# Q1_STM32_Buck_MCU.net
KiCad netlist of a schematic drawn in Altium Designer
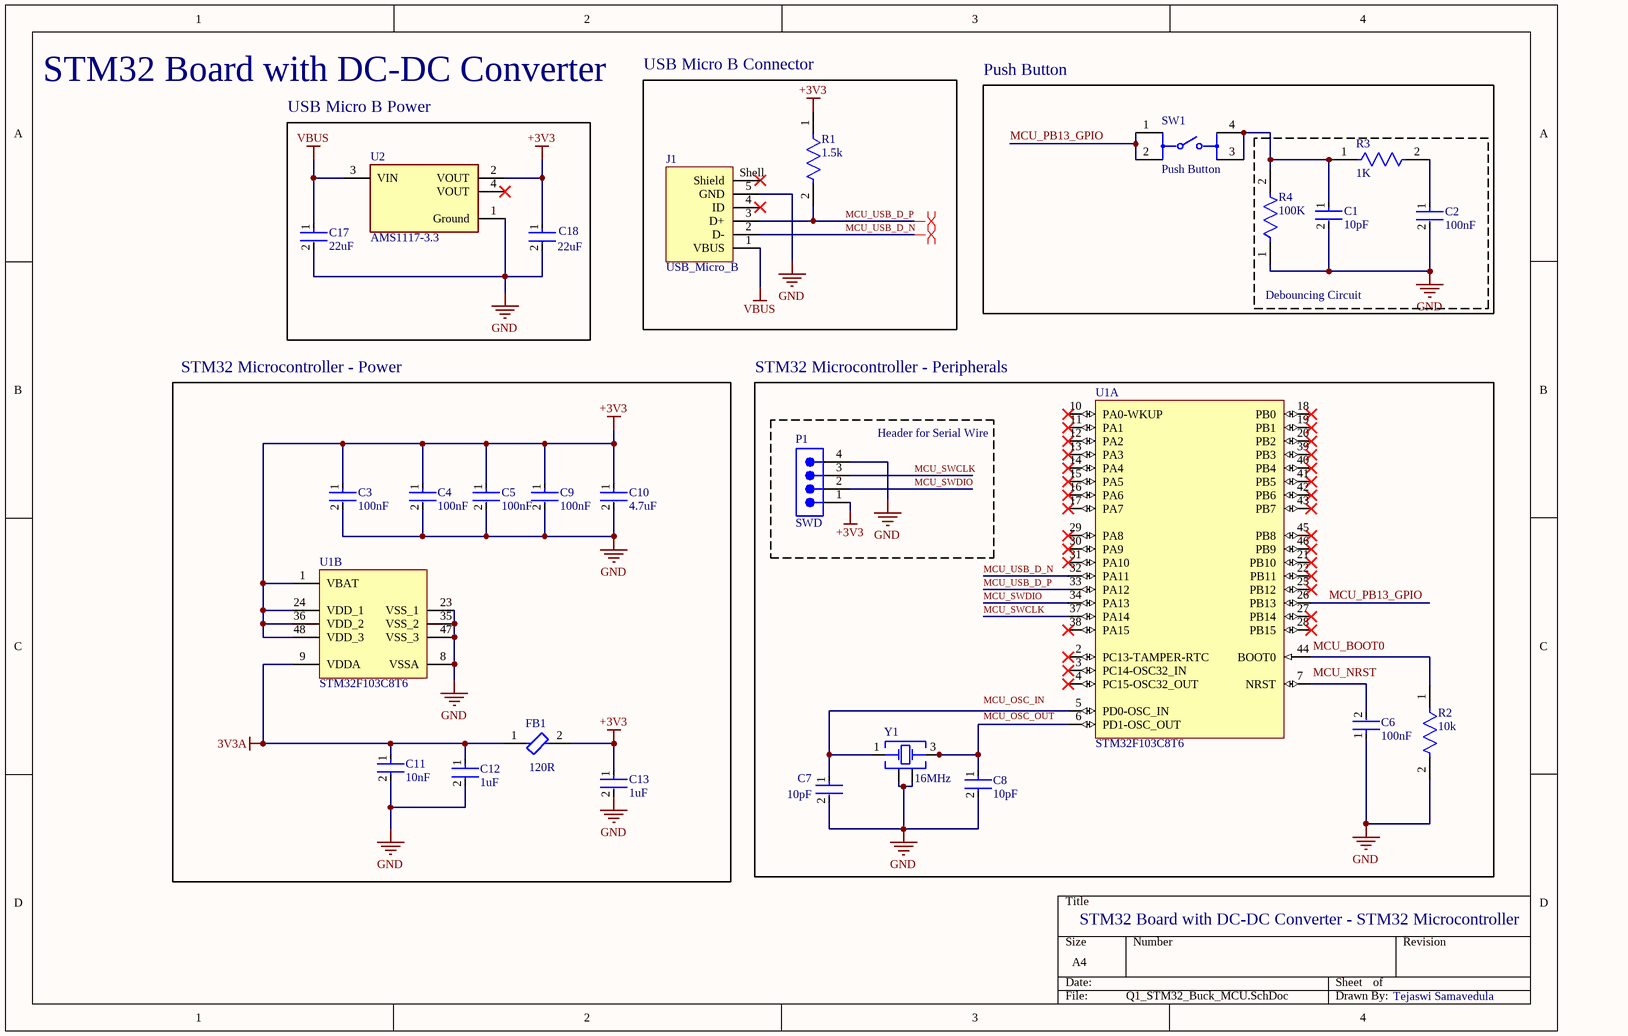
[diagram p0: Q1_STM32_Buck_MCU.SchDoc]

(export (version "E")
  (design (tool "Eeschema 10.0.6"))
  (components
    (comp (ref "C1")
      (value "10pF")
      (footprint "FP-CC0402-MFG")
      (description "CAP CER 0.1UF 16V X5R 0402")
      (fields
        (field (name "OCTOPART") "https://octopart.com/cc0402mrx5r7bb104-yageo-33242280")
        (field (name "MANUFACTURER PART NUMBER") "CC0402MRX5R7BB104")
      )
      (libsource (lib "Altium Content Vault") (part "11868f565c42a9108669ba33697ecf6"))
    )
    (comp (ref "C2")
      (value "100nF")
      (footprint "FP-CC0402-MFG")
      (description "CAP CER 0.1UF 16V X5R 0402")
      (fields
        (field (name "OCTOPART") "https://octopart.com/cc0402mrx5r7bb104-yageo-33242280")
        (field (name "MANUFACTURER PART NUMBER") "CC0402MRX5R7BB104")
      )
      (libsource (lib "Altium Content Vault") (part "11868f565c42a9108669ba33697ecf6"))
    )
    (comp (ref "C3")
      (value "100nF")
      (footprint "FP-CC0402-MFG")
      (description "CAP CER 0.1UF 16V X5R 0402")
      (fields
        (field (name "OCTOPART") "https://octopart.com/cc0402mrx5r7bb104-yageo-33242280")
        (field (name "MANUFACTURER PART NUMBER") "CC0402MRX5R7BB104")
      )
      (libsource (lib "Altium Content Vault") (part "11868f565c42a9108669ba33697ecf6"))
    )
    (comp (ref "C4")
      (value "100nF")
      (footprint "FP-CC0402-MFG")
      (description "CAP CER 0.1UF 16V X5R 0402")
      (fields
        (field (name "OCTOPART") "https://octopart.com/cc0402mrx5r7bb104-yageo-33242280")
        (field (name "MANUFACTURER PART NUMBER") "CC0402MRX5R7BB104")
      )
      (libsource (lib "Altium Content Vault") (part "11868f565c42a9108669ba33697ecf6"))
    )
    (comp (ref "C5")
      (value "100nF")
      (footprint "FP-CC0402-MFG")
      (description "CAP CER 0.1UF 16V X5R 0402")
      (fields
        (field (name "OCTOPART") "https://octopart.com/cc0402mrx5r7bb104-yageo-33242280")
        (field (name "MANUFACTURER PART NUMBER") "CC0402MRX5R7BB104")
      )
      (libsource (lib "Altium Content Vault") (part "11868f565c42a9108669ba33697ecf6"))
    )
    (comp (ref "C6")
      (value "100nF")
      (footprint "FP-CC0402-MFG")
      (description "CAP CER 0.1UF 16V X5R 0402")
      (fields
        (field (name "OCTOPART") "https://octopart.com/cc0402mrx5r7bb104-yageo-33242280")
        (field (name "MANUFACTURER PART NUMBER") "CC0402MRX5R7BB104")
      )
      (libsource (lib "Altium Content Vault") (part "11868f565c42a9108669ba33697ecf6"))
    )
    (comp (ref "C7")
      (value "10pF")
      (footprint "FP-CC0402-MFG")
      (description "CAP CER 0.1UF 16V X5R 0402")
      (fields
        (field (name "OCTOPART") "https://octopart.com/cc0402mrx5r7bb104-yageo-33242280")
        (field (name "MANUFACTURER PART NUMBER") "CC0402MRX5R7BB104")
      )
      (libsource (lib "Altium Content Vault") (part "11868f565c42a9108669ba33697ecf6"))
    )
    (comp (ref "C8")
      (value "10pF")
      (footprint "FP-CC0402-MFG")
      (description "CAP CER 0.1UF 16V X5R 0402")
      (fields
        (field (name "OCTOPART") "https://octopart.com/cc0402mrx5r7bb104-yageo-33242280")
        (field (name "MANUFACTURER PART NUMBER") "CC0402MRX5R7BB104")
      )
      (libsource (lib "Altium Content Vault") (part "11868f565c42a9108669ba33697ecf6"))
    )
    (comp (ref "C9")
      (value "100nF")
      (footprint "FP-CC0402-MFG")
      (description "CAP CER 0.1UF 16V X5R 0402")
      (fields
        (field (name "OCTOPART") "https://octopart.com/cc0402mrx5r7bb104-yageo-33242280")
        (field (name "MANUFACTURER PART NUMBER") "CC0402MRX5R7BB104")
      )
      (libsource (lib "Altium Content Vault") (part "11868f565c42a9108669ba33697ecf6"))
    )
    (comp (ref "C10")
      (value "4.7uF")
      (footprint "FP-GRM188-0_2-IPC_A")
      (description "Chip Multilayer Ceramic Capacitors for General Purpose, 0603, 4.7uF, X7S, 22%, 10%, 16V")
      (fields (field (name "TOLERANCE") "10%"))
      (libsource (lib "Altium Content Vault") (part "11868f565c42a9108669ba33697ecf6"))
    )
    (comp (ref "C11")
      (value "10nF")
      (footprint "FP-CC0402-MFG")
      (description "CAP CER 0.1UF 16V X5R 0402")
      (fields
        (field (name "OCTOPART") "https://octopart.com/cc0402mrx5r7bb104-yageo-33242280")
        (field (name "MANUFACTURER PART NUMBER") "CC0402MRX5R7BB104")
      )
      (libsource (lib "Altium Content Vault") (part "11868f565c42a9108669ba33697ecf6"))
    )
    (comp (ref "C12")
      (value "1uF")
      (footprint "FP-CC0402-MFG")
      (description "CAP CER 0.1UF 16V X5R 0402")
      (fields
        (field (name "OCTOPART") "https://octopart.com/cc0402mrx5r7bb104-yageo-33242280")
        (field (name "MANUFACTURER PART NUMBER") "CC0402MRX5R7BB104")
      )
      (libsource (lib "Altium Content Vault") (part "11868f565c42a9108669ba33697ecf6"))
    )
    (comp (ref "C13")
      (value "1uF")
      (footprint "FP-CC0402-MFG")
      (description "CAP CER 0.1UF 16V X5R 0402")
      (fields
        (field (name "OCTOPART") "https://octopart.com/cc0402mrx5r7bb104-yageo-33242280")
        (field (name "MANUFACTURER PART NUMBER") "CC0402MRX5R7BB104")
      )
      (libsource (lib "Altium Content Vault") (part "11868f565c42a9108669ba33697ecf6"))
    )
    (comp (ref "C17")
      (value "22uF")
      (footprint "FP-GRM188-0_2-IPC_C")
      (description "Chip Multilayer Ceramic Capacitors for General Purpose, 0603, 22uF, X5R, 15%, 20%, 10V")
      (fields (field (name "TOLERANCE") "20%"))
      (libsource (lib "Altium Content Vault") (part "11868f565c42a9108669ba33697ecf6"))
    )
    (comp (ref "C18")
      (value "22uF")
      (footprint "FP-GRM188-0_2-IPC_C")
      (description "Chip Multilayer Ceramic Capacitors for General Purpose, 0603, 22uF, X5R, 15%, 20%, 10V")
      (fields (field (name "TOLERANCE") "20%"))
      (libsource (lib "Altium Content Vault") (part "11868f565c42a9108669ba33697ecf6"))
    )
    (comp (ref "FB1")
      (value "120R")
      (footprint "FP-BLM15-0_05-IPC_B")
      (description "Chip Ferrite Bead, 0402, 1000Ω @ 100MHz, 0.65Ω, 25%, 300mA")
      (fields (field (name "TOLERANCE") "25%"))
      (libsource (lib "Altium Content Vault") (part "5f30dd21d616792df468990f7003faa"))
    )
    (comp (ref "J1")
      (value "USB_Micro_B")
      (footprint "629105150521")
      (libsource (lib "Altium Content Vault") (part "Micro USB 2.0_Type B_Receptacle_1 Port"))
    )
    (comp (ref "P1")
      (value "SWD")
      (footprint "61300411121")
      (libsource (lib "Altium Content Vault") (part "Header_Male_1R_04P"))
    )
    (comp (ref "R1")
      (value "1.5k")
      (footprint "FP-ERA2A-MFG")
      (description "RES SMD 10K OHM 0.1% 1/16W 0402")
      (fields (field (name "TOLERANCE") "0.1%") (field (name "MANUFACTURER PART NUMBER") "ERA-2AEB103X"))
      (libsource (lib "Altium Content Vault") (part "1029c3af85768c4190bb7ad29bc67b5"))
    )
    (comp (ref "R2")
      (value "10k")
      (footprint "FP-ERA2A-MFG")
      (description "RES SMD 10K OHM 0.1% 1/16W 0402")
      (fields (field (name "TOLERANCE") "0.1%") (field (name "MANUFACTURER PART NUMBER") "ERA-2AEB103X"))
      (libsource (lib "Altium Content Vault") (part "1029c3af85768c4190bb7ad29bc67b5"))
    )
    (comp (ref "R3")
      (value "1K")
      (footprint "FP-RCA0603-e3-MFG")
      (fields (field (name "TOLERANCE") "1%"))
      (libsource (lib "Altium Content Vault") (part "1029c3af85768c4190bb7ad29bc67b5"))
    )
    (comp (ref "R4")
      (value "100K")
      (footprint "FP-RK73H1J-IPC_C")
      (description "100kΩ ±1% 0.1W Chip Resistor 0603 Thick Film AEC-Q200 Qualified")
      (fields (field (name "TOLERANCE") "1%"))
      (libsource (lib "Altium Content Vault") (part "1029c3af85768c4190bb7ad29bc67b5"))
    )
    (comp (ref "SW1")
      (value "Push Button")
      (footprint "FP-1977223-1-MFG")
      (description "1977223-1 Pushbutton Switch, SPST, Momentary, 0.05A, 24VDC, Solder Terminal, Panel Mount")
      (libsource (lib "Altium Content Vault") (part "8567d77f6c555f6be97cf75406a5984"))
    )
    (comp (ref "U1")
      (value "STM32F103C8T6")
      (footprint "STM-LQFP48_L")
      (libsource (lib "Altium Content Vault") (part "MC-ARM-STM32F103X8_B-SQ48"))
    )
    (comp (ref "U2")
      (value "AMS1117-3.3")
      (footprint "FP-AMS1117-IPC_C")
      (description "LDO Voltage Regulators 1A, 3.3V")
      (fields
        (field (name "OCTOPART") "https://octopart.com/ams1117-3.3-advanced+monolithic+systems-25899300")
        (field (name "MANUFACTURER") "Advanced Monolithic Systems")
      )
      (libsource (lib "Altium Content Vault") (part "8bdbb5f8e77002000e30dd2845d0354"))
    )
    (comp (ref "Y1")
      (value "16MHz")
      (footprint "WE-XTAL_IQXC-42")
      (description "830108288709 WE-XTAL Quartz Crystal")
      (libsource (lib "Altium Content Vault") (part "WE-XTAL_IQXC-42"))
    )
  )
  (nets
    (net (code "1") (name "+3V3") (class "Default")
      (node (ref "C10") (pin "1") (pinfunction "1_1") (pintype "passive"))
      (node (ref "C13") (pin "1") (pinfunction "1_1") (pintype "passive"))
      (node (ref "C18") (pin "1") (pinfunction "1_1") (pintype "passive"))
      (node (ref "C3") (pin "1") (pinfunction "1_1") (pintype "passive"))
      (node (ref "C4") (pin "1") (pinfunction "1_1") (pintype "passive"))
      (node (ref "C5") (pin "1") (pinfunction "1_1") (pintype "passive"))
      (node (ref "C9") (pin "1") (pinfunction "1_1") (pintype "passive"))
      (node (ref "FB1") (pin "2") (pinfunction "2_2") (pintype "passive"))
      (node (ref "P1") (pin "1") (pinfunction "1_1") (pintype "passive"))
      (node (ref "R1") (pin "1") (pinfunction "1_1") (pintype "passive"))
      (node (ref "U1") (pin "1") (pinfunction "VBAT_1") (pintype "power_in"))
      (node (ref "U1") (pin "24") (pinfunction "VDD_1_24") (pintype "power_in"))
      (node (ref "U1") (pin "36") (pinfunction "VDD_2_36") (pintype "power_in"))
      (node (ref "U1") (pin "48") (pinfunction "VDD_3_48") (pintype "power_in"))
      (node (ref "U2") (pin "2") (pinfunction "VOUT_2") (pintype "passive"))
    )
    (net (code "6") (name "/MCU_PB13_GPIO") (class "Default")
      (node (ref "SW1") (pin "1") (pinfunction "1_1") (pintype "passive"))
      (node (ref "SW1") (pin "2") (pinfunction "2_2") (pintype "passive"))
      (node (ref "U1") (pin "26") (pinfunction "PB13_26") (pintype "bidirectional"))
    )
    (net (code "7") (name "/MCU_SWCLK") (class "Default")
      (node (ref "P1") (pin "3") (pinfunction "3_3") (pintype "passive"))
      (node (ref "U1") (pin "37") (pinfunction "PA14_37") (pintype "bidirectional"))
    )
    (net (code "8") (name "/MCU_SWDIO") (class "Default")
      (node (ref "P1") (pin "2") (pinfunction "2_2") (pintype "passive"))
      (node (ref "U1") (pin "34") (pinfunction "PA13_34") (pintype "bidirectional"))
    )
    (net (code "9") (name "/MCU_USB_D_N") (class "Default")
      (node (ref "J1") (pin "2") (pinfunction "D-_2") (pintype "passive"))
      (node (ref "U1") (pin "32") (pinfunction "PA11_32") (pintype "bidirectional"))
    )
    (net (code "10") (name "/MCU_USB_D_P") (class "Default")
      (node (ref "J1") (pin "3") (pinfunction "D+_3") (pintype "passive"))
      (node (ref "R1") (pin "2") (pinfunction "2_2") (pintype "passive"))
      (node (ref "U1") (pin "33") (pinfunction "PA12_33") (pintype "bidirectional"))
    )
    (net (code "11") (name "3V3A") (class "Default")
      (node (ref "C11") (pin "1") (pinfunction "1_1") (pintype "passive"))
      (node (ref "C12") (pin "1") (pinfunction "1_1") (pintype "passive"))
      (node (ref "FB1") (pin "1") (pinfunction "1_1") (pintype "passive"))
      (node (ref "U1") (pin "9") (pinfunction "VDDA_9") (pintype "power_in"))
    )
    (net (code "12") (name "GND") (class "Default")
      (node (ref "C1") (pin "2") (pinfunction "2_2") (pintype "passive"))
      (node (ref "C10") (pin "2") (pinfunction "2_2") (pintype "passive"))
      (node (ref "C11") (pin "2") (pinfunction "2_2") (pintype "passive"))
      (node (ref "C12") (pin "2") (pinfunction "2_2") (pintype "passive"))
      (node (ref "C13") (pin "2") (pinfunction "2_2") (pintype "passive"))
      (node (ref "C17") (pin "2") (pinfunction "2_2") (pintype "passive"))
      (node (ref "C18") (pin "2") (pinfunction "2_2") (pintype "passive"))
      (node (ref "C2") (pin "2") (pinfunction "2_2") (pintype "passive"))
      (node (ref "C3") (pin "2") (pinfunction "2_2") (pintype "passive"))
      (node (ref "C4") (pin "2") (pinfunction "2_2") (pintype "passive"))
      (node (ref "C5") (pin "2") (pinfunction "2_2") (pintype "passive"))
      (node (ref "C6") (pin "1") (pinfunction "1_1") (pintype "passive"))
      (node (ref "C7") (pin "2") (pinfunction "2_2") (pintype "passive"))
      (node (ref "C8") (pin "2") (pinfunction "2_2") (pintype "passive"))
      (node (ref "C9") (pin "2") (pinfunction "2_2") (pintype "passive"))
      (node (ref "J1") (pin "5") (pinfunction "GND_5") (pintype "passive"))
      (node (ref "P1") (pin "4") (pinfunction "4_4") (pintype "passive"))
      (node (ref "R2") (pin "2") (pinfunction "2_2") (pintype "passive"))
      (node (ref "R4") (pin "1") (pinfunction "1_1") (pintype "passive"))
      (node (ref "U1") (pin "23") (pinfunction "VSS_1_23") (pintype "power_in"))
      (node (ref "U1") (pin "35") (pinfunction "VSS_2_35") (pintype "power_in"))
      (node (ref "U1") (pin "47") (pinfunction "VSS_3_47") (pintype "power_in"))
      (node (ref "U1") (pin "8") (pinfunction "VSSA_8") (pintype "power_in"))
      (node (ref "U2") (pin "1") (pinfunction "Ground_1") (pintype "power_in"))
      (node (ref "Y1") (pin "2") (pinfunction "GND_2") (pintype "passive"))
      (node (ref "Y1") (pin "4") (pinfunction "GND_4") (pintype "passive"))
    )
    (net (code "13") (name "Net-(C1-Pad1)") (class "Default")
      (node (ref "C1") (pin "1") (pinfunction "1_1") (pintype "passive"))
      (node (ref "R3") (pin "1") (pinfunction "1_1") (pintype "passive"))
      (node (ref "R4") (pin "2") (pinfunction "2_2") (pintype "passive"))
      (node (ref "SW1") (pin "3") (pinfunction "3_3") (pintype "passive"))
      (node (ref "SW1") (pin "4") (pinfunction "4_4") (pintype "passive"))
    )
    (net (code "14") (name "Net-(C2-Pad1)") (class "Default")
      (node (ref "C2") (pin "1") (pinfunction "1_1") (pintype "passive"))
      (node (ref "R3") (pin "2") (pinfunction "2_2") (pintype "passive"))
    )
    (net (code "15") (name "Net-(U1A-BOOT0)") (class "Default")
      (node (ref "R2") (pin "1") (pinfunction "1_1") (pintype "passive"))
      (node (ref "U1") (pin "44") (pinfunction "BOOT0_44") (pintype "input"))
    )
    (net (code "16") (name "Net-(U1A-NRST)") (class "Default")
      (node (ref "C6") (pin "2") (pinfunction "2_2") (pintype "passive"))
      (node (ref "U1") (pin "7") (pinfunction "NRST_7") (pintype "bidirectional"))
    )
    (net (code "17") (name "Net-(U1A-PD0-OSC_IN)") (class "Default")
      (node (ref "C7") (pin "1") (pinfunction "1_1") (pintype "passive"))
      (node (ref "U1") (pin "5") (pinfunction "PD0-OSC_IN_5") (pintype "bidirectional"))
      (node (ref "Y1") (pin "1") (pinfunction "Crystal_1") (pintype "passive"))
    )
    (net (code "18") (name "Net-(U1A-PD1-OSC_OUT)") (class "Default")
      (node (ref "C8") (pin "1") (pinfunction "1_1") (pintype "passive"))
      (node (ref "U1") (pin "6") (pinfunction "PD1-OSC_OUT_6") (pintype "bidirectional"))
      (node (ref "Y1") (pin "3") (pinfunction "Crystal_3") (pintype "passive"))
    )
    (net (code "19") (name "VBUS") (class "Default")
      (node (ref "C17") (pin "1") (pinfunction "1_1") (pintype "passive"))
      (node (ref "J1") (pin "1") (pinfunction "VBUS_1") (pintype "passive"))
      (node (ref "U2") (pin "3") (pinfunction "VIN_3") (pintype "power_in"))
    )
    (net (code "20") (name "unconnected-(J1-ID-Pad4)") (class "Default")
      (node (ref "J1") (pin "4") (pinfunction "ID_4") (pintype "passive+no_connect"))
    )
    (net (code "21") (name "unconnected-(J1-Shield-PadShell)") (class "Default")
      (node (ref "J1") (pin "Shell") (pinfunction "Shield_Shell") (pintype "passive+no_connect"))
    )
    (net (code "22") (name "unconnected-(U1A-PA0-WKUP-Pad10)") (class "Default")
      (node (ref "U1") (pin "10") (pinfunction "PA0-WKUP_10") (pintype "bidirectional+no_connect"))
    )
    (net (code "23") (name "unconnected-(U1A-PA1-Pad11)") (class "Default")
      (node (ref "U1") (pin "11") (pinfunction "PA1_11") (pintype "bidirectional+no_connect"))
    )
    (net (code "24") (name "unconnected-(U1A-PA2-Pad12)") (class "Default")
      (node (ref "U1") (pin "12") (pinfunction "PA2_12") (pintype "bidirectional+no_connect"))
    )
    (net (code "25") (name "unconnected-(U1A-PA3-Pad13)") (class "Default")
      (node (ref "U1") (pin "13") (pinfunction "PA3_13") (pintype "bidirectional+no_connect"))
    )
    (net (code "26") (name "unconnected-(U1A-PA4-Pad14)") (class "Default")
      (node (ref "U1") (pin "14") (pinfunction "PA4_14") (pintype "bidirectional+no_connect"))
    )
    (net (code "27") (name "unconnected-(U1A-PA5-Pad15)") (class "Default")
      (node (ref "U1") (pin "15") (pinfunction "PA5_15") (pintype "bidirectional+no_connect"))
    )
    (net (code "28") (name "unconnected-(U1A-PA6-Pad16)") (class "Default")
      (node (ref "U1") (pin "16") (pinfunction "PA6_16") (pintype "bidirectional+no_connect"))
    )
    (net (code "29") (name "unconnected-(U1A-PA7-Pad17)") (class "Default")
      (node (ref "U1") (pin "17") (pinfunction "PA7_17") (pintype "bidirectional+no_connect"))
    )
    (net (code "30") (name "unconnected-(U1A-PA8-Pad29)") (class "Default")
      (node (ref "U1") (pin "29") (pinfunction "PA8_29") (pintype "bidirectional+no_connect"))
    )
    (net (code "31") (name "unconnected-(U1A-PA9-Pad30)") (class "Default")
      (node (ref "U1") (pin "30") (pinfunction "PA9_30") (pintype "bidirectional+no_connect"))
    )
    (net (code "32") (name "unconnected-(U1A-PA10-Pad31)") (class "Default")
      (node (ref "U1") (pin "31") (pinfunction "PA10_31") (pintype "bidirectional+no_connect"))
    )
    (net (code "33") (name "unconnected-(U1A-PA15-Pad38)") (class "Default")
      (node (ref "U1") (pin "38") (pinfunction "PA15_38") (pintype "bidirectional+no_connect"))
    )
    (net (code "34") (name "unconnected-(U1A-PB0-Pad18)") (class "Default")
      (node (ref "U1") (pin "18") (pinfunction "PB0_18") (pintype "bidirectional+no_connect"))
    )
    (net (code "35") (name "unconnected-(U1A-PB1-Pad19)") (class "Default")
      (node (ref "U1") (pin "19") (pinfunction "PB1_19") (pintype "bidirectional+no_connect"))
    )
    (net (code "36") (name "unconnected-(U1A-PB2-Pad20)") (class "Default")
      (node (ref "U1") (pin "20") (pinfunction "PB2_20") (pintype "bidirectional+no_connect"))
    )
    (net (code "37") (name "unconnected-(U1A-PB3-Pad39)") (class "Default")
      (node (ref "U1") (pin "39") (pinfunction "PB3_39") (pintype "bidirectional+no_connect"))
    )
    (net (code "38") (name "unconnected-(U1A-PB4-Pad40)") (class "Default")
      (node (ref "U1") (pin "40") (pinfunction "PB4_40") (pintype "bidirectional+no_connect"))
    )
    (net (code "39") (name "unconnected-(U1A-PB5-Pad41)") (class "Default")
      (node (ref "U1") (pin "41") (pinfunction "PB5_41") (pintype "bidirectional+no_connect"))
    )
    (net (code "40") (name "unconnected-(U1A-PB6-Pad42)") (class "Default")
      (node (ref "U1") (pin "42") (pinfunction "PB6_42") (pintype "bidirectional+no_connect"))
    )
    (net (code "41") (name "unconnected-(U1A-PB7-Pad43)") (class "Default")
      (node (ref "U1") (pin "43") (pinfunction "PB7_43") (pintype "bidirectional+no_connect"))
    )
    (net (code "42") (name "unconnected-(U1A-PB8-Pad45)") (class "Default")
      (node (ref "U1") (pin "45") (pinfunction "PB8_45") (pintype "bidirectional+no_connect"))
    )
    (net (code "43") (name "unconnected-(U1A-PB9-Pad46)") (class "Default")
      (node (ref "U1") (pin "46") (pinfunction "PB9_46") (pintype "bidirectional+no_connect"))
    )
    (net (code "44") (name "unconnected-(U1A-PB10-Pad21)") (class "Default")
      (node (ref "U1") (pin "21") (pinfunction "PB10_21") (pintype "bidirectional+no_connect"))
    )
    (net (code "45") (name "unconnected-(U1A-PB11-Pad22)") (class "Default")
      (node (ref "U1") (pin "22") (pinfunction "PB11_22") (pintype "bidirectional+no_connect"))
    )
    (net (code "46") (name "unconnected-(U1A-PB12-Pad25)") (class "Default")
      (node (ref "U1") (pin "25") (pinfunction "PB12_25") (pintype "bidirectional+no_connect"))
    )
    (net (code "47") (name "unconnected-(U1A-PB14-Pad27)") (class "Default")
      (node (ref "U1") (pin "27") (pinfunction "PB14_27") (pintype "bidirectional+no_connect"))
    )
    (net (code "48") (name "unconnected-(U1A-PB15-Pad28)") (class "Default")
      (node (ref "U1") (pin "28") (pinfunction "PB15_28") (pintype "bidirectional+no_connect"))
    )
    (net (code "49") (name "unconnected-(U1A-PC13-TAMPER-RTC-Pad2)") (class "Default")
      (node (ref "U1") (pin "2") (pinfunction "PC13-TAMPER-RTC_2") (pintype "bidirectional+no_connect"))
    )
    (net (code "50") (name "unconnected-(U1A-PC14-OSC32_IN-Pad3)") (class "Default")
      (node (ref "U1") (pin "3") (pinfunction "PC14-OSC32_IN_3") (pintype "bidirectional+no_connect"))
    )
    (net (code "51") (name "unconnected-(U1A-PC15-OSC32_OUT-Pad4)") (class "Default")
      (node (ref "U1") (pin "4") (pinfunction "PC15-OSC32_OUT_4") (pintype "bidirectional+no_connect"))
    )
    (net (code "52") (name "unconnected-(U2-VOUT-Pad4)") (class "Default")
      (node (ref "U2") (pin "4") (pinfunction "VOUT_4") (pintype "passive+no_connect"))
    )
  )
)
